# Sheet-NODE-V1_1.net
KiCad netlist of a schematic drawn in Altium Designer
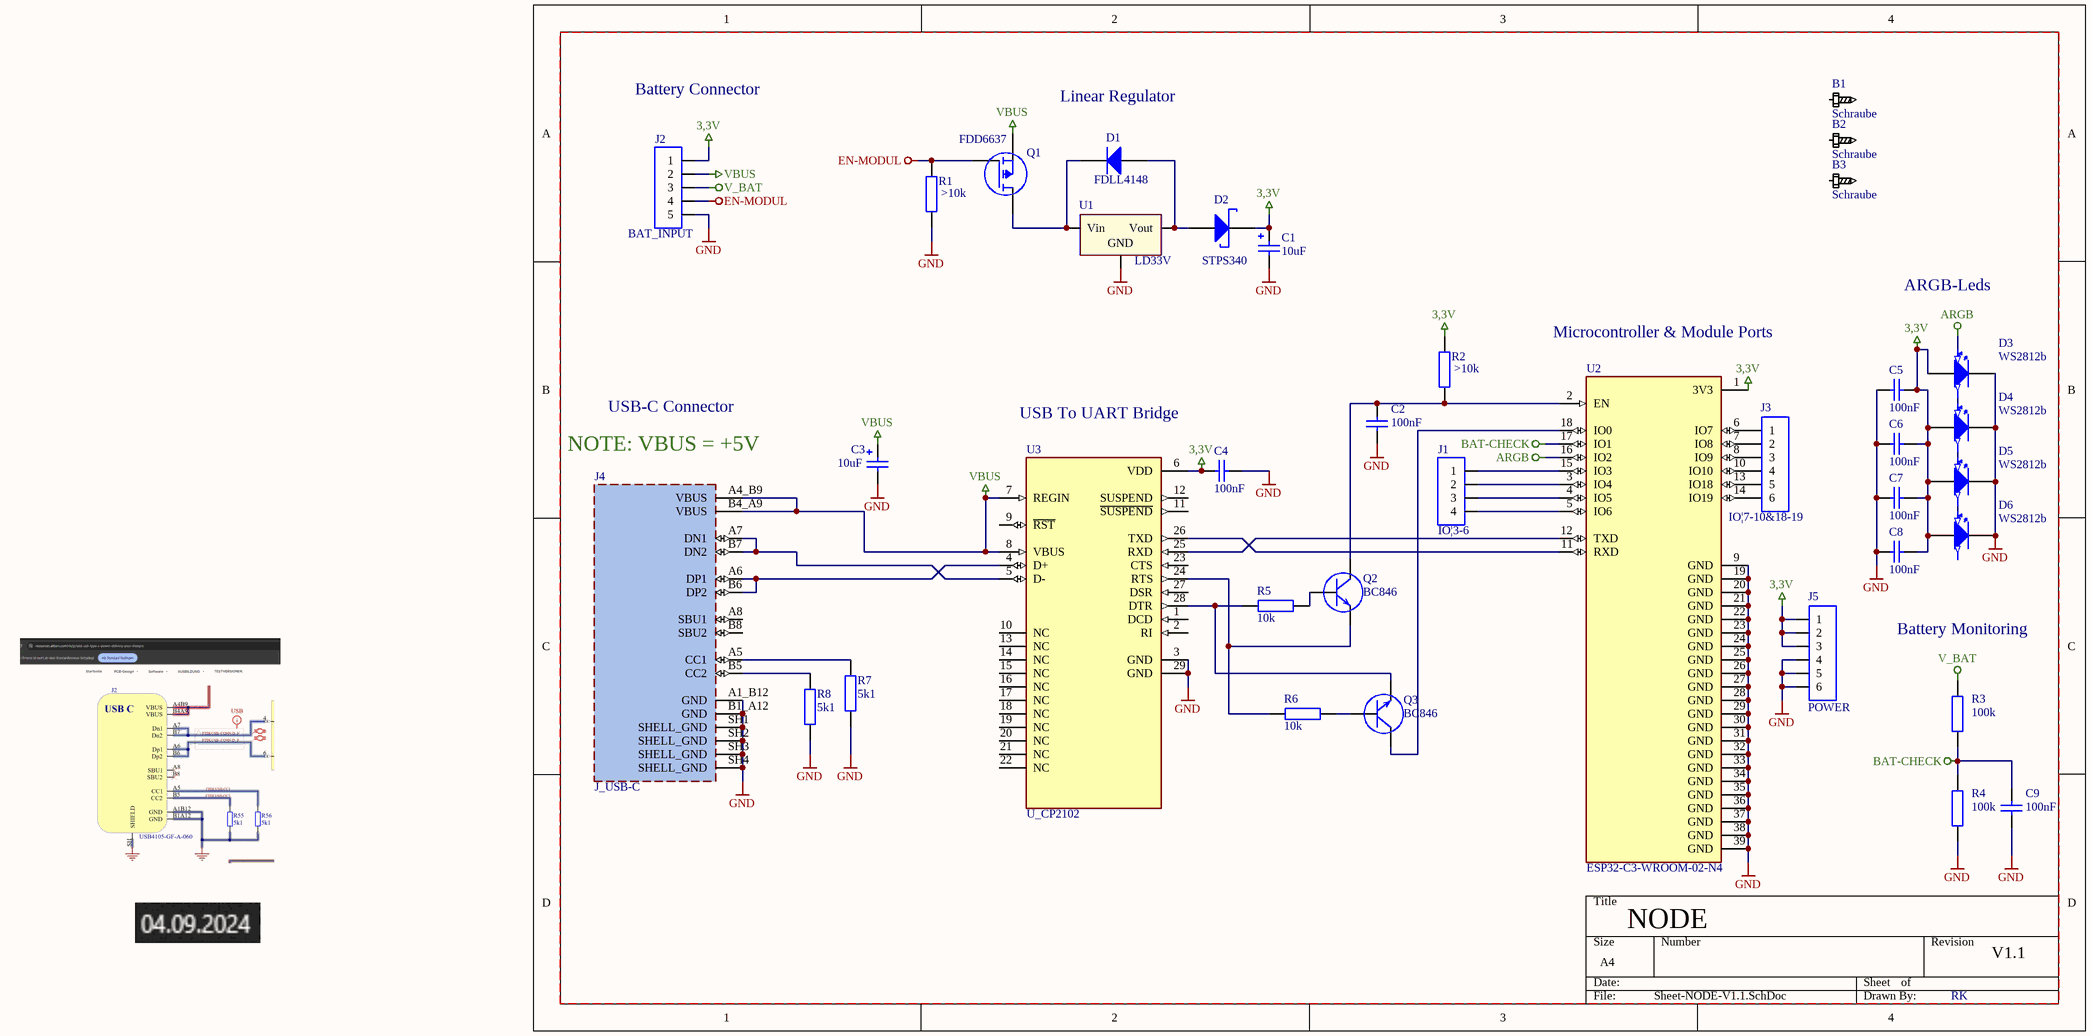
[diagram p0: Sheet-NODE-V1.1.SchDoc]

(export (version "E")
  (design (tool "Eeschema 10.0.6"))
  (components
    (comp (ref "B1")
      (value "Schraube")
      (footprint "B_Schraube-M3 PAD")
      (description "Schraubenloch für M3 Schrauben")
      (libsource (lib "SCHLIB-PCSB_5.1.3") (part "B_Schraube"))
    )
    (comp (ref "B2")
      (value "Schraube")
      (footprint "B_Schraube-M3 PAD")
      (description "Schraubenloch für M3 Schrauben")
      (libsource (lib "SCHLIB-PCSB_5.1.3") (part "B_Schraube"))
    )
    (comp (ref "B3")
      (value "Schraube")
      (footprint "B_Schraube-M3 PAD")
      (description "Schraubenloch für M3 Schrauben")
      (libsource (lib "SCHLIB-PCSB_5.1.3") (part "B_Schraube"))
    )
    (comp (ref "C1")
      (value "10uF")
      (footprint "C_SMD_B-Typ")
      (description "SMD Elektrolytkondensator")
      (libsource (lib "SCHLIB-PCSB_5.1.3") (part "C_SMD_ELK"))
    )
    (comp (ref "C2")
      (value "100nF")
      (footprint "C_SMD_0603")
      (description "Kondensator SMD Universal, Keramik, Folie, usw.")
      (libsource (lib "SCHLIB-PCSB_5.1.3") (part "C_SMD_KO"))
    )
    (comp (ref "C3")
      (value "10uF")
      (footprint "C_SMD_B-Typ")
      (description "SMD Elektrolytkondensator")
      (libsource (lib "SCHLIB-PCSB_5.1.3") (part "C_SMD_ELK"))
    )
    (comp (ref "C4")
      (value "100nF")
      (footprint "C_SMD_0603")
      (description "Kondensator SMD Universal, Keramik, Folie, usw.")
      (libsource (lib "SCHLIB-PCSB_5.1.3") (part "C_SMD_KO"))
    )
    (comp (ref "C5")
      (value "100nF")
      (footprint "C_SMD_0603")
      (description "Kondensator SMD Universal, Keramik, Folie, usw.")
      (libsource (lib "SCHLIB-PCSB_5.1.3") (part "C_SMD_KO"))
    )
    (comp (ref "C6")
      (value "100nF")
      (footprint "C_SMD_0603")
      (description "Kondensator SMD Universal, Keramik, Folie, usw.")
      (libsource (lib "SCHLIB-PCSB_5.1.3") (part "C_SMD_KO"))
    )
    (comp (ref "C7")
      (value "100nF")
      (footprint "C_SMD_0603")
      (description "Kondensator SMD Universal, Keramik, Folie, usw.")
      (libsource (lib "SCHLIB-PCSB_5.1.3") (part "C_SMD_KO"))
    )
    (comp (ref "C8")
      (value "100nF")
      (footprint "C_SMD_0603")
      (description "Kondensator SMD Universal, Keramik, Folie, usw.")
      (libsource (lib "SCHLIB-PCSB_5.1.3") (part "C_SMD_KO"))
    )
    (comp (ref "C9")
      (value "100nF")
      (footprint "C_SMD_0603")
      (description "Kondensator SMD Universal, Keramik, Folie, usw.")
      (libsource (lib "SCHLIB-PCSB_5.1.3") (part "C_SMD_KO"))
    )
    (comp (ref "D1")
      (value "FDLL4148")
      (footprint "SOD-80-2")
      (description "Diode SMD Silizium")
      (libsource (lib "SCHLIB-PCSB_5.1.3") (part "D_SMD_Silizium"))
    )
    (comp (ref "D2")
      (value "STPS340")
      (footprint "D_DO-214")
      (description "Diode SMD Schottky")
      (libsource (lib "SCHLIB-PCSB_5.1.3") (part "D_SMD_Schottky"))
    )
    (comp (ref "D3")
      (value "WS2812b")
      (footprint "D_SMD_LED-ARGB")
      (description "Diode SMD ARGB")
      (libsource (lib "SCHLIB-PCSB_5.1.3") (part "D_SMD_LED-ARGB"))
    )
    (comp (ref "D4")
      (value "WS2812b")
      (footprint "D_SMD_LED-ARGB")
      (description "Diode SMD ARGB")
      (libsource (lib "SCHLIB-PCSB_5.1.3") (part "D_SMD_LED-ARGB"))
    )
    (comp (ref "D5")
      (value "WS2812b")
      (footprint "D_SMD_LED-ARGB")
      (description "Diode SMD ARGB")
      (libsource (lib "SCHLIB-PCSB_5.1.3") (part "D_SMD_LED-ARGB"))
    )
    (comp (ref "D6")
      (value "WS2812b")
      (footprint "D_SMD_LED-ARGB")
      (description "Diode SMD ARGB")
      (libsource (lib "SCHLIB-PCSB_5.1.3") (part "D_SMD_LED-ARGB"))
    )
    (comp (ref "J1")
      (value "IO¦3-6")
      (footprint "Sip-4")
      (description "Stecker")
      (libsource (lib "SCHLIB-PCSB_5.1.3") (part "J_THT_CON4"))
    )
    (comp (ref "J2")
      (value "BAT_INPUT")
      (footprint "SIP-5")
      (description "Stecker")
      (libsource (lib "SCHLIB-PCSB_5.1.3") (part "J_THT_CON5"))
    )
    (comp (ref "J3")
      (value "IO¦7-10&18-19")
      (footprint "SIP-6")
      (description "Stecker")
      (libsource (lib "SCHLIB-PCSB_5.1.3") (part "J_THT_CON6"))
    )
    (comp (ref "J4")
      (value "J_USB-C")
      (footprint "GCT_USB4105-GF-A")
      (description "USB4105-GF-")
      (fields (field (name "MF") "{'manufacturer': u'GCT'}") (field (name "MP") "USB4105-GF-A"))
      (libsource (lib "SCHLIB-PCSB_5.1.3") (part "J_USB-C"))
    )
    (comp (ref "J5")
      (value "POWER")
      (footprint "SIP-6")
      (description "Stecker")
      (libsource (lib "SCHLIB-PCSB_5.1.3") (part "J_THT_CON6"))
    )
    (comp (ref "Q1")
      (value "FDD6637")
      (footprint "FDD6637_TO-252-3")
      (description "P-Kanal MOSFET")
      (fields (field (name "MP") "IRFZ44NPBF") (field (name "DIGI-KEY_PART_NUMBER") "IRFZ44NPBF-ND"))
      (libsource (lib "SCHLIB-PCSB_5.1.3") (part "Q_SMD_MOSFET-P-Kanal"))
    )
    (comp (ref "Q2")
      (value "BC846")
      (footprint "SOT-23-3_BC846")
      (description "NPN Transistor")
      (libsource (lib "SCHLIB-PCSB_5.1.3") (part "Q_SMD_NPN"))
    )
    (comp (ref "Q3")
      (value "BC846")
      (footprint "SOT-23-3_BC846")
      (description "NPN Transistor")
      (libsource (lib "SCHLIB-PCSB_5.1.3") (part "Q_SMD_NPN"))
    )
    (comp (ref "R1")
      (value ">10k")
      (footprint "R_SMD_0805")
      (description "Widerstand SMD")
      (libsource (lib "SCHLIB-PCSB_5.1.3") (part "R_SMD_Widerstand"))
    )
    (comp (ref "R2")
      (value ">10k")
      (footprint "R_SMD_0805")
      (description "Widerstand SMD")
      (libsource (lib "SCHLIB-PCSB_5.1.3") (part "R_SMD_Widerstand"))
    )
    (comp (ref "R3")
      (value "100k")
      (footprint "R_SMD_0805")
      (description "Widerstand SMD")
      (libsource (lib "SCHLIB-PCSB_5.1.3") (part "R_SMD_Widerstand"))
    )
    (comp (ref "R4")
      (value "100k")
      (footprint "R_SMD_0805")
      (description "Widerstand SMD")
      (libsource (lib "SCHLIB-PCSB_5.1.3") (part "R_SMD_Widerstand"))
    )
    (comp (ref "R5")
      (value "10k")
      (footprint "R_SMD_0805")
      (description "Widerstand SMD")
      (libsource (lib "SCHLIB-PCSB_5.1.3") (part "R_SMD_Widerstand"))
    )
    (comp (ref "R6")
      (value "10k")
      (footprint "R_SMD_0805")
      (description "Widerstand SMD")
      (libsource (lib "SCHLIB-PCSB_5.1.3") (part "R_SMD_Widerstand"))
    )
    (comp (ref "R7")
      (value "5k1")
      (footprint "R_SMD_0805")
      (description "Widerstand SMD")
      (libsource (lib "SCHLIB-PCSB_5.1.3") (part "R_SMD_Widerstand"))
    )
    (comp (ref "R8")
      (value "5k1")
      (footprint "R_SMD_0805")
      (description "Widerstand SMD")
      (libsource (lib "SCHLIB-PCSB_5.1.3") (part "R_SMD_Widerstand"))
    )
    (comp (ref "U1")
      (value "LD33V")
      (footprint "TO-220-3V")
      (description "Linearwandler")
      (libsource (lib "SCHLIB-PCSB_5.1.3") (part "U_THT_78xx"))
    )
    (comp (ref "U2")
      (value "ESP32-C3-WROOM-02-N4")
      (footprint "MODULE_ESP32-C3-WROOM-02-H4")
      (fields (field (name "MF") "Espressif Systems"))
      (libsource (lib "SCHLIB-PCSB_5.1.3") (part "ESP32-C3-WROOM-02-N4"))
    )
    (comp (ref "U3")
      (value "U_CP2102")
      (footprint "QFN50P500X500X100-29N")
      (description "CP2102N USB 2.0 to UART (RS232) Bridge Interface Evaluation Board")
      (fields (field (name "MF") "Silicon Labs") (field (name "MP") "CP2102"))
      (libsource (lib "SCHLIB-PCSB_5.1.3") (part "U_CP2102"))
    )
  )
  (nets
    (net (code "1") (name "3,3V") (class "Default")
      (node (ref "C1") (pin "1") (pinfunction "1_1") (pintype "passive"))
      (node (ref "C4") (pin "1") (pintype "passive"))
      (node (ref "C5") (pin "2") (pintype "passive"))
      (node (ref "C6") (pin "2") (pintype "passive"))
      (node (ref "C7") (pin "2") (pintype "passive"))
      (node (ref "C8") (pin "2") (pintype "passive"))
      (node (ref "D2") (pin "2") (pinfunction "K_2") (pintype "passive"))
      (node (ref "D3") (pin "1") (pinfunction "VDD_1") (pintype "passive"))
      (node (ref "D4") (pin "1") (pinfunction "VDD_1") (pintype "passive"))
      (node (ref "D5") (pin "1") (pinfunction "VDD_1") (pintype "passive"))
      (node (ref "D6") (pin "1") (pinfunction "VDD_1") (pintype "passive"))
      (node (ref "J2") (pin "1") (pinfunction "1_1") (pintype "passive"))
      (node (ref "J5") (pin "1") (pinfunction "1_1") (pintype "passive"))
      (node (ref "J5") (pin "2") (pinfunction "2_2") (pintype "passive"))
      (node (ref "J5") (pin "3") (pinfunction "3_3") (pintype "passive"))
      (node (ref "R2") (pin "2") (pintype "passive"))
      (node (ref "U2") (pin "1") (pinfunction "3V3_1") (pintype "power_in"))
      (node (ref "U3") (pin "6") (pinfunction "VDD_6") (pintype "power_in"))
    )
    (net (code "2") (name "ARGB") (class "Default")
      (node (ref "D3") (pin "4") (pinfunction "DIN_4") (pintype "input"))
      (node (ref "U2") (pin "16") (pinfunction "IO2_16") (pintype "bidirectional"))
    )
    (net (code "3") (name "BAT-CHECK") (class "Default")
      (node (ref "C9") (pin "2") (pintype "passive"))
      (node (ref "R3") (pin "1") (pintype "passive"))
      (node (ref "R4") (pin "2") (pintype "passive"))
      (node (ref "U2") (pin "17") (pinfunction "IO1_17") (pintype "bidirectional"))
    )
    (net (code "4") (name "EN-MODUL") (class "Default")
      (node (ref "J2") (pin "4") (pinfunction "4_4") (pintype "passive"))
      (node (ref "Q1") (pin "G") (pinfunction "G_G") (pintype "passive"))
      (node (ref "R1") (pin "2") (pintype "passive"))
    )
    (net (code "5") (name "GND") (class "Default")
      (node (ref "C1") (pin "2") (pinfunction "2_2") (pintype "passive"))
      (node (ref "C2") (pin "1") (pintype "passive"))
      (node (ref "C3") (pin "2") (pinfunction "2_2") (pintype "passive"))
      (node (ref "C4") (pin "2") (pintype "passive"))
      (node (ref "C5") (pin "1") (pintype "passive"))
      (node (ref "C6") (pin "1") (pintype "passive"))
      (node (ref "C7") (pin "1") (pintype "passive"))
      (node (ref "C8") (pin "1") (pintype "passive"))
      (node (ref "C9") (pin "1") (pintype "passive"))
      (node (ref "D3") (pin "3") (pinfunction "GND_3") (pintype "passive"))
      (node (ref "D4") (pin "3") (pinfunction "GND_3") (pintype "passive"))
      (node (ref "D5") (pin "3") (pinfunction "GND_3") (pintype "passive"))
      (node (ref "D6") (pin "3") (pinfunction "GND_3") (pintype "passive"))
      (node (ref "J2") (pin "5") (pinfunction "5_5") (pintype "passive"))
      (node (ref "J4") (pin "A1_B12") (pinfunction "GND_A1_B12") (pintype "power_in"))
      (node (ref "J4") (pin "B1_A12") (pinfunction "GND_B1_A12") (pintype "power_in"))
      (node (ref "J4") (pin "SH1") (pinfunction "SHELL_GND_SH1") (pintype "power_in"))
      (node (ref "J4") (pin "SH2") (pinfunction "SHELL_GND_SH2") (pintype "power_in"))
      (node (ref "J4") (pin "SH3") (pinfunction "SHELL_GND_SH3") (pintype "power_in"))
      (node (ref "J4") (pin "SH4") (pinfunction "SHELL_GND_SH4") (pintype "power_in"))
      (node (ref "J5") (pin "4") (pinfunction "4_4") (pintype "passive"))
      (node (ref "J5") (pin "5") (pinfunction "5_5") (pintype "passive"))
      (node (ref "J5") (pin "6") (pinfunction "6_6") (pintype "passive"))
      (node (ref "R1") (pin "1") (pintype "passive"))
      (node (ref "R4") (pin "1") (pintype "passive"))
      (node (ref "R7") (pin "1") (pintype "passive"))
      (node (ref "R8") (pin "1") (pintype "passive"))
      (node (ref "U1") (pin "3") (pinfunction "GND_3") (pintype "passive"))
      (node (ref "U2") (pin "19") (pinfunction "GND_19") (pintype "power_in"))
      (node (ref "U2") (pin "20") (pinfunction "GND_20") (pintype "power_in"))
      (node (ref "U2") (pin "21") (pinfunction "GND_21") (pintype "power_in"))
      (node (ref "U2") (pin "22") (pinfunction "GND_22") (pintype "power_in"))
      (node (ref "U2") (pin "23") (pinfunction "GND_23") (pintype "power_in"))
      (node (ref "U2") (pin "24") (pinfunction "GND_24") (pintype "power_in"))
      (node (ref "U2") (pin "25") (pinfunction "GND_25") (pintype "power_in"))
      (node (ref "U2") (pin "26") (pinfunction "GND_26") (pintype "power_in"))
      (node (ref "U2") (pin "27") (pinfunction "GND_27") (pintype "power_in"))
      (node (ref "U2") (pin "28") (pinfunction "GND_28") (pintype "power_in"))
      (node (ref "U2") (pin "29") (pinfunction "GND_29") (pintype "power_in"))
      (node (ref "U2") (pin "30") (pinfunction "GND_30") (pintype "power_in"))
      (node (ref "U2") (pin "31") (pinfunction "GND_31") (pintype "power_in"))
      (node (ref "U2") (pin "32") (pinfunction "GND_32") (pintype "power_in"))
      (node (ref "U2") (pin "33") (pinfunction "GND_33") (pintype "power_in"))
      (node (ref "U2") (pin "34") (pinfunction "GND_34") (pintype "power_in"))
      (node (ref "U2") (pin "35") (pinfunction "GND_35") (pintype "power_in"))
      (node (ref "U2") (pin "36") (pinfunction "GND_36") (pintype "power_in"))
      (node (ref "U2") (pin "37") (pinfunction "GND_37") (pintype "power_in"))
      (node (ref "U2") (pin "38") (pinfunction "GND_38") (pintype "power_in"))
      (node (ref "U2") (pin "39") (pinfunction "GND_39") (pintype "power_in"))
      (node (ref "U2") (pin "9") (pinfunction "GND_9") (pintype "power_in"))
      (node (ref "U3") (pin "29") (pinfunction "GND_29") (pintype "power_in"))
      (node (ref "U3") (pin "3") (pinfunction "GND_3") (pintype "power_in"))
    )
    (net (code "6") (name "Net-(D1-A)") (class "Default")
      (node (ref "D1") (pin "1") (pinfunction "A_1") (pintype "passive"))
      (node (ref "D2") (pin "1") (pinfunction "A_1") (pintype "passive"))
      (node (ref "U1") (pin "2") (pinfunction "Vout_2") (pintype "passive"))
    )
    (net (code "7") (name "Net-(D1-K)") (class "Default")
      (node (ref "D1") (pin "2") (pinfunction "K_2") (pintype "passive"))
      (node (ref "Q1") (pin "D") (pinfunction "D_D") (pintype "passive"))
      (node (ref "U1") (pin "1") (pinfunction "Vin_1") (pintype "passive"))
    )
    (net (code "8") (name "Net-(D3-DOUT)") (class "Default")
      (node (ref "D3") (pin "2") (pinfunction "DOUT_2") (pintype "output"))
      (node (ref "D4") (pin "4") (pinfunction "DIN_4") (pintype "input"))
    )
    (net (code "9") (name "Net-(D4-DOUT)") (class "Default")
      (node (ref "D4") (pin "2") (pinfunction "DOUT_2") (pintype "output"))
      (node (ref "D5") (pin "4") (pinfunction "DIN_4") (pintype "input"))
    )
    (net (code "10") (name "Net-(D5-DOUT)") (class "Default")
      (node (ref "D5") (pin "2") (pinfunction "DOUT_2") (pintype "output"))
      (node (ref "D6") (pin "4") (pinfunction "DIN_4") (pintype "input"))
    )
    (net (code "11") (name "Net-(J4-CC1)") (class "Default")
      (node (ref "J4") (pin "A5") (pinfunction "CC1_A5") (pintype "bidirectional"))
      (node (ref "R7") (pin "2") (pintype "passive"))
    )
    (net (code "12") (name "Net-(J4-CC2)") (class "Default")
      (node (ref "J4") (pin "B5") (pinfunction "CC2_B5") (pintype "bidirectional"))
      (node (ref "R8") (pin "2") (pintype "passive"))
    )
    (net (code "13") (name "Net-(J4-DN1)") (class "Default")
      (node (ref "J4") (pin "A7") (pinfunction "DN1_A7") (pintype "bidirectional"))
      (node (ref "J4") (pin "B7") (pinfunction "DN2_B7") (pintype "bidirectional"))
      (node (ref "U3") (pin "5") (pinfunction "D-_5") (pintype "bidirectional"))
    )
    (net (code "14") (name "Net-(J4-DP1)") (class "Default")
      (node (ref "J4") (pin "A6") (pinfunction "DP1_A6") (pintype "bidirectional"))
      (node (ref "J4") (pin "B6") (pinfunction "DP2_B6") (pintype "bidirectional"))
      (node (ref "U3") (pin "4") (pinfunction "D+_4") (pintype "bidirectional"))
    )
    (net (code "15") (name "Net-(Q2-PadB)") (class "Default")
      (node (ref "Q2") (pin "B") (pinfunction "B_B") (pintype "passive"))
      (node (ref "R5") (pin "2") (pintype "passive"))
    )
    (net (code "16") (name "Net-(Q3-PadB)") (class "Default")
      (node (ref "Q3") (pin "B") (pinfunction "B_B") (pintype "passive"))
      (node (ref "R6") (pin "2") (pintype "passive"))
    )
    (net (code "17") (name "Net-(U2-EN)") (class "Default")
      (node (ref "C2") (pin "2") (pintype "passive"))
      (node (ref "Q2") (pin "C") (pinfunction "C_C") (pintype "passive"))
      (node (ref "R2") (pin "1") (pintype "passive"))
      (node (ref "U2") (pin "2") (pinfunction "EN_2") (pintype "input"))
    )
    (net (code "18") (name "Net-(U2-IO0)") (class "Default")
      (node (ref "Q3") (pin "C") (pinfunction "C_C") (pintype "passive"))
      (node (ref "U2") (pin "18") (pinfunction "IO0_18") (pintype "bidirectional"))
    )
    (net (code "19") (name "Net-(U2-IO3)") (class "Default")
      (node (ref "J1") (pin "1") (pinfunction "1_1") (pintype "passive"))
      (node (ref "U2") (pin "15") (pinfunction "IO3_15") (pintype "bidirectional"))
    )
    (net (code "20") (name "Net-(U2-IO4)") (class "Default")
      (node (ref "J1") (pin "2") (pinfunction "2_2") (pintype "passive"))
      (node (ref "U2") (pin "3") (pinfunction "IO4_3") (pintype "bidirectional"))
    )
    (net (code "21") (name "Net-(U2-IO5)") (class "Default")
      (node (ref "J1") (pin "3") (pinfunction "3_3") (pintype "passive"))
      (node (ref "U2") (pin "4") (pinfunction "IO5_4") (pintype "bidirectional"))
    )
    (net (code "22") (name "Net-(U2-IO6)") (class "Default")
      (node (ref "J1") (pin "4") (pinfunction "4_4") (pintype "passive"))
      (node (ref "U2") (pin "5") (pinfunction "IO6_5") (pintype "bidirectional"))
    )
    (net (code "23") (name "Net-(U2-IO7)") (class "Default")
      (node (ref "J3") (pin "1") (pinfunction "1_1") (pintype "passive"))
      (node (ref "U2") (pin "6") (pinfunction "IO7_6") (pintype "bidirectional"))
    )
    (net (code "24") (name "Net-(U2-IO8)") (class "Default")
      (node (ref "J3") (pin "2") (pinfunction "2_2") (pintype "passive"))
      (node (ref "U2") (pin "7") (pinfunction "IO8_7") (pintype "bidirectional"))
    )
    (net (code "25") (name "Net-(U2-IO9)") (class "Default")
      (node (ref "J3") (pin "3") (pinfunction "3_3") (pintype "passive"))
      (node (ref "U2") (pin "8") (pinfunction "IO9_8") (pintype "bidirectional"))
    )
    (net (code "26") (name "Net-(U2-IO10)") (class "Default")
      (node (ref "J3") (pin "4") (pinfunction "4_4") (pintype "passive"))
      (node (ref "U2") (pin "10") (pinfunction "IO10_10") (pintype "bidirectional"))
    )
    (net (code "27") (name "Net-(U2-IO18)") (class "Default")
      (node (ref "J3") (pin "5") (pinfunction "5_5") (pintype "passive"))
      (node (ref "U2") (pin "13") (pinfunction "IO18_13") (pintype "bidirectional"))
    )
    (net (code "28") (name "Net-(U2-IO19)") (class "Default")
      (node (ref "J3") (pin "6") (pinfunction "6_6") (pintype "passive"))
      (node (ref "U2") (pin "14") (pinfunction "IO19_14") (pintype "bidirectional"))
    )
    (net (code "29") (name "Net-(U2-RXD)") (class "Default")
      (node (ref "U2") (pin "11") (pinfunction "RXD_11") (pintype "bidirectional"))
      (node (ref "U3") (pin "26") (pinfunction "TXD_26") (pintype "output"))
    )
    (net (code "30") (name "Net-(U2-TXD)") (class "Default")
      (node (ref "U2") (pin "12") (pinfunction "TXD_12") (pintype "bidirectional"))
      (node (ref "U3") (pin "25") (pinfunction "RXD_25") (pintype "input"))
    )
    (net (code "31") (name "Net-(U3-DTR)") (class "Default")
      (node (ref "Q3") (pin "E") (pinfunction "E_E") (pintype "passive"))
      (node (ref "R5") (pin "1") (pintype "passive"))
      (node (ref "U3") (pin "28") (pinfunction "DTR_28") (pintype "output"))
    )
    (net (code "32") (name "Net-(U3-RTS)") (class "Default")
      (node (ref "Q2") (pin "E") (pinfunction "E_E") (pintype "passive"))
      (node (ref "R6") (pin "1") (pintype "passive"))
      (node (ref "U3") (pin "24") (pinfunction "RTS_24") (pintype "output"))
    )
    (net (code "33") (name "VBUS") (class "Default")
      (node (ref "C3") (pin "1") (pinfunction "1_1") (pintype "passive"))
      (node (ref "J2") (pin "2") (pinfunction "2_2") (pintype "passive"))
      (node (ref "J4") (pin "A4_B9") (pinfunction "VBUS_A4_B9") (pintype "power_in"))
      (node (ref "J4") (pin "B4_A9") (pinfunction "VBUS_B4_A9") (pintype "power_in"))
      (node (ref "Q1") (pin "S") (pinfunction "S_S") (pintype "passive"))
      (node (ref "U3") (pin "7") (pinfunction "REGIN_7") (pintype "input"))
      (node (ref "U3") (pin "8") (pinfunction "VBUS_8") (pintype "input"))
    )
    (net (code "34") (name "V_BAT") (class "Default")
      (node (ref "J2") (pin "3") (pinfunction "3_3") (pintype "passive"))
      (node (ref "R3") (pin "2") (pintype "passive"))
    )
    (net (code "35") (name "unconnected-(B1-PAD-Pad1)") (class "Default")
      (node (ref "B1") (pin "1") (pinfunction "PAD_1") (pintype "passive"))
    )
    (net (code "36") (name "unconnected-(B2-PAD-Pad1)") (class "Default")
      (node (ref "B2") (pin "1") (pinfunction "PAD_1") (pintype "passive"))
    )
    (net (code "37") (name "unconnected-(B3-PAD-Pad1)") (class "Default")
      (node (ref "B3") (pin "1") (pinfunction "PAD_1") (pintype "passive"))
    )
    (net (code "38") (name "unconnected-(D6-DOUT-Pad2)") (class "Default")
      (node (ref "D6") (pin "2") (pinfunction "DOUT_2") (pintype "output"))
    )
    (net (code "39") (name "unconnected-(J4-SBU1-PadA8)") (class "Default")
      (node (ref "J4") (pin "A8") (pinfunction "SBU1_A8") (pintype "bidirectional"))
    )
    (net (code "40") (name "unconnected-(J4-SBU2-PadB8)") (class "Default")
      (node (ref "J4") (pin "B8") (pinfunction "SBU2_B8") (pintype "bidirectional"))
    )
    (net (code "41") (name "unconnected-(U3-CTS-Pad23)") (class "Default")
      (node (ref "U3") (pin "23") (pinfunction "CTS_23") (pintype "input"))
    )
    (net (code "42") (name "unconnected-(U3-DCD-Pad1)") (class "Default")
      (node (ref "U3") (pin "1") (pinfunction "DCD_1") (pintype "input"))
    )
    (net (code "43") (name "unconnected-(U3-DSR-Pad27)") (class "Default")
      (node (ref "U3") (pin "27") (pinfunction "DSR_27") (pintype "input"))
    )
    (net (code "44") (name "unconnected-(U3-NC-Pad10)") (class "Default")
      (node (ref "U3") (pin "10") (pinfunction "NC_10") (pintype "passive"))
    )
    (net (code "45") (name "unconnected-(U3-NC-Pad13)") (class "Default")
      (node (ref "U3") (pin "13") (pinfunction "NC_13") (pintype "passive"))
    )
    (net (code "46") (name "unconnected-(U3-NC-Pad14)") (class "Default")
      (node (ref "U3") (pin "14") (pinfunction "NC_14") (pintype "passive"))
    )
    (net (code "47") (name "unconnected-(U3-NC-Pad15)") (class "Default")
      (node (ref "U3") (pin "15") (pinfunction "NC_15") (pintype "passive"))
    )
    (net (code "48") (name "unconnected-(U3-NC-Pad16)") (class "Default")
      (node (ref "U3") (pin "16") (pinfunction "NC_16") (pintype "passive"))
    )
    (net (code "49") (name "unconnected-(U3-NC-Pad17)") (class "Default")
      (node (ref "U3") (pin "17") (pinfunction "NC_17") (pintype "passive"))
    )
    (net (code "50") (name "unconnected-(U3-NC-Pad18)") (class "Default")
      (node (ref "U3") (pin "18") (pinfunction "NC_18") (pintype "passive"))
    )
    (net (code "51") (name "unconnected-(U3-NC-Pad19)") (class "Default")
      (node (ref "U3") (pin "19") (pinfunction "NC_19") (pintype "passive"))
    )
    (net (code "52") (name "unconnected-(U3-NC-Pad20)") (class "Default")
      (node (ref "U3") (pin "20") (pinfunction "NC_20") (pintype "passive"))
    )
    (net (code "53") (name "unconnected-(U3-NC-Pad21)") (class "Default")
      (node (ref "U3") (pin "21") (pinfunction "NC_21") (pintype "passive"))
    )
    (net (code "54") (name "unconnected-(U3-NC-Pad22)") (class "Default")
      (node (ref "U3") (pin "22") (pinfunction "NC_22") (pintype "passive"))
    )
    (net (code "55") (name "unconnected-(U3-RI-Pad2)") (class "Default")
      (node (ref "U3") (pin "2") (pinfunction "RI_2") (pintype "input"))
    )
    (net (code "56") (name "unconnected-(U3-SUSPEND-Pad12)") (class "Default")
      (node (ref "U3") (pin "12") (pinfunction "SUSPEND_12") (pintype "output"))
    )
    (net (code "57") (name "unconnected-(U3-~{RST}-Pad9)") (class "Default")
      (node (ref "U3") (pin "9") (pinfunction "~{RST}_9") (pintype "bidirectional"))
    )
    (net (code "58") (name "unconnected-(U3-~{SUSPEND}-Pad11)") (class "Default")
      (node (ref "U3") (pin "11") (pinfunction "~{SUSPEND}_11") (pintype "output"))
    )
  )
)
